# 612_jetracer.net
KiCad netlist of a schematic drawn in EAGLE
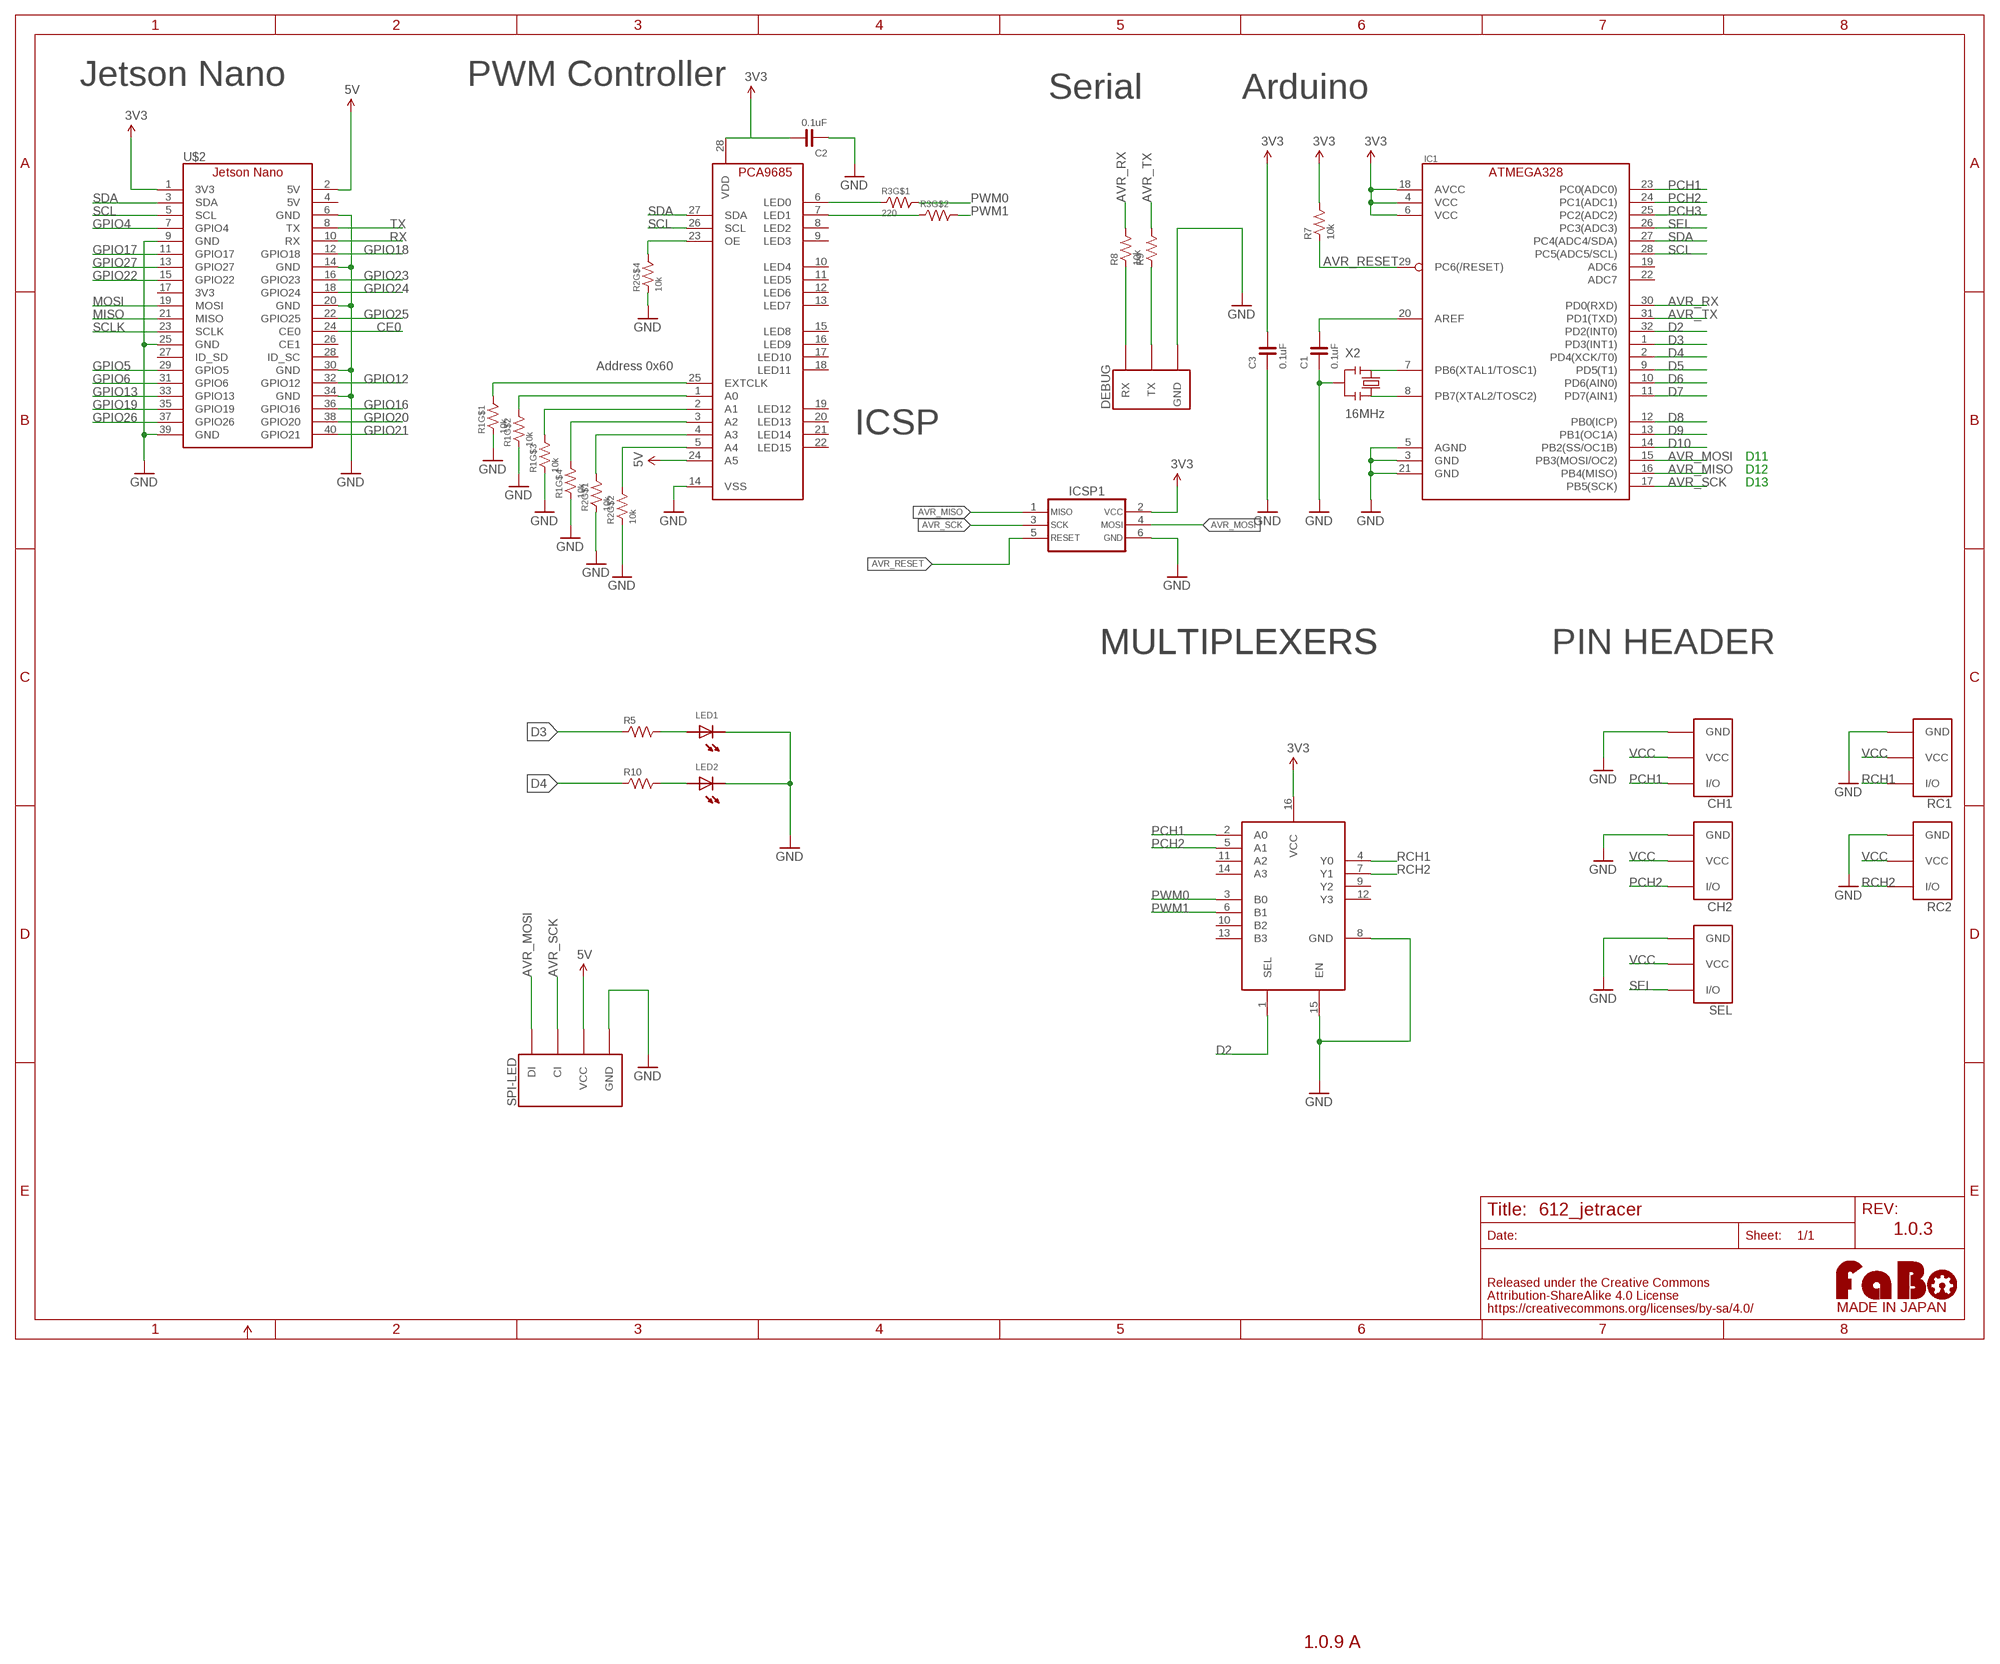
[diagram p0: schematic, sheet 1]

(export (version "E")
  (design (tool "Eeschema 10.0.6"))
  (components
    (comp (ref "C1")
      (value "0.1uF")
      (footprint "eagle-import:0603")
      (libsource (lib "eagle-import") (part "CAPACITOR-0603"))
    )
    (comp (ref "C2")
      (value "0.1uF")
      (footprint "eagle-import:0603")
      (libsource (lib "eagle-import") (part "CAPACITOR-0603"))
    )
    (comp (ref "C3")
      (value "0.1uF")
      (footprint "eagle-import:0603")
      (libsource (lib "eagle-import") (part "CAPACITOR-0603"))
    )
    (comp (ref "CH1")
      (value "FABO_BRICK_3PIN-HEADER")
      (footprint "eagle-import:FABO_BRICK_3PIN_HEADER")
      (libsource (lib "eagle-import") (part "FABO_BRICK_3PIN-HEADER"))
    )
    (comp (ref "CH2")
      (value "FABO_BRICK_3PIN-HEADER")
      (footprint "eagle-import:FABO_BRICK_3PIN_HEADER")
      (libsource (lib "eagle-import") (part "FABO_BRICK_3PIN-HEADER"))
    )
    (comp (ref "DEBUG")
      (value "FABO_BRICK_3PIN_DEBUG")
      (footprint "eagle-import:FABO_BRICK_3PIN_DEBUG")
      (libsource (lib "eagle-import") (part "FABO_BRICK_3PIN_DEBUG"))
    )
    (comp (ref "IC1")
      (value "ATMEGA328P-AU")
      (footprint "eagle-import:TQFP-32")
      (libsource (lib "eagle-import") (part "ATMEGA328P-AU"))
    )
    (comp (ref "IC3")
      (value "MULTIPLEXERSMC74HC157A")
      (footprint "eagle-import:TSSOP-16")
      (libsource (lib "eagle-import") (part "MULTIPLEXERSMC74HC157A"))
    )
    (comp (ref "ICSP1")
      (value "ICSP_AVR-TC_NOHOLE")
      (footprint "eagle-import:TC2030")
      (libsource (lib "eagle-import") (part "ICSP_AVR-TC_NOHOLE"))
    )
    (comp (ref "LED1")
      (value "LED-0603")
      (footprint "eagle-import:0603")
      (libsource (lib "eagle-import") (part "LED-0603"))
    )
    (comp (ref "LED2")
      (value "LED-0603")
      (footprint "eagle-import:0603")
      (libsource (lib "eagle-import") (part "LED-0603"))
    )
    (comp (ref "R1")
      (value "10k")
      (footprint "eagle-import:EXBV8V")
      (libsource (lib "eagle-import") (part "RESISTOR_ARRAY"))
    )
    (comp (ref "R2")
      (value "10k")
      (footprint "eagle-import:EXBV8V")
      (libsource (lib "eagle-import") (part "RESISTOR_ARRAY"))
    )
    (comp (ref "R3")
      (value "220")
      (footprint "eagle-import:EXBV8V")
      (libsource (lib "eagle-import") (part "RESISTOR_ARRAY"))
    )
    (comp (ref "R5")
      (value "10k")
      (footprint "eagle-import:0603")
      (libsource (lib "eagle-import") (part "RESISTOR-0603"))
    )
    (comp (ref "R7")
      (value "10k")
      (footprint "eagle-import:0603")
      (libsource (lib "eagle-import") (part "RESISTOR-0603"))
    )
    (comp (ref "R8")
      (value "10k")
      (footprint "eagle-import:0603")
      (libsource (lib "eagle-import") (part "RESISTOR-0603"))
    )
    (comp (ref "R9")
      (value "10k")
      (footprint "eagle-import:0603")
      (libsource (lib "eagle-import") (part "RESISTOR-0603"))
    )
    (comp (ref "R10")
      (value "10k")
      (footprint "eagle-import:0603")
      (libsource (lib "eagle-import") (part "RESISTOR-0603"))
    )
    (comp (ref "RC1")
      (value "FABO_BRICK_3PIN-HEADER")
      (footprint "eagle-import:FABO_BRICK_3PIN_HEADER")
      (libsource (lib "eagle-import") (part "FABO_BRICK_3PIN-HEADER"))
    )
    (comp (ref "RC2")
      (value "FABO_BRICK_3PIN-HEADER")
      (footprint "eagle-import:FABO_BRICK_3PIN_HEADER")
      (libsource (lib "eagle-import") (part "FABO_BRICK_3PIN-HEADER"))
    )
    (comp (ref "SEL")
      (value "FABO_BRICK_3PIN-HEADER")
      (footprint "eagle-import:FABO_BRICK_3PIN_HEADER")
      (libsource (lib "eagle-import") (part "FABO_BRICK_3PIN-HEADER"))
    )
    (comp (ref "SPI-LED")
      (value "FABO-SPI-LED-B04B")
      (footprint "eagle-import:SPI-B04B-PASK-1")
      (libsource (lib "eagle-import") (part "FABO-SPI-LED-B04B"))
    )
    (comp (ref "U$2")
      (value "JETSON_NANO_NOBORDER")
      (footprint "eagle-import:JETSON_NANO_NOBOARDER")
      (libsource (lib "eagle-import") (part "JETSON_NANO_NOBORDER"))
    )
    (comp (ref "U$9")
      (value "PCA9685")
      (footprint "eagle-import:PCA9685")
      (libsource (lib "eagle-import") (part "PCA9685"))
    )
    (comp (ref "U$14")
      (value "LOGO_FABO-M")
      (footprint "eagle-import:LOGO_FABO_MS")
      (libsource (lib "eagle-import") (part "LOGO_FABO-M"))
    )
    (comp (ref "X2")
      (value "16MHz")
      (footprint "eagle-import:CSTNE_V_C")
      (libsource (lib "eagle-import") (part "RESONATOR"))
    )
  )
  (nets
    (net (code "1") (name "/AVR_RX") (class "Default")
      (node (ref "IC1") (pin "30") (pinfunction "PD0(RXD)_30") (pintype "bidirectional"))
      (node (ref "R8") (pin "2") (pinfunction "2_2") (pintype "bidirectional"))
    )
    (net (code "2") (name "/AVR_TX") (class "Default")
      (node (ref "IC1") (pin "31") (pinfunction "PD1(TXD)_31") (pintype "bidirectional"))
      (node (ref "R9") (pin "2") (pinfunction "2_2") (pintype "bidirectional"))
    )
    (net (code "3") (name "/CE0") (class "Default")
      (node (ref "U$2") (pin "24") (pinfunction "CE0_24") (pintype "bidirectional"))
    )
    (net (code "4") (name "/D2") (class "Default")
      (node (ref "IC1") (pin "32") (pinfunction "PD2(INT0)_32") (pintype "bidirectional"))
      (node (ref "IC3") (pin "1") (pinfunction "SEL_1") (pintype "bidirectional"))
    )
    (net (code "5") (name "/D5") (class "Default")
      (node (ref "IC1") (pin "9") (pinfunction "PD5(T1)_9") (pintype "bidirectional"))
    )
    (net (code "6") (name "/D6") (class "Default")
      (node (ref "IC1") (pin "10") (pinfunction "PD6(AIN0)_10") (pintype "bidirectional"))
    )
    (net (code "7") (name "/D7") (class "Default")
      (node (ref "IC1") (pin "11") (pinfunction "PD7(AIN1)_11") (pintype "bidirectional"))
    )
    (net (code "8") (name "/D8") (class "Default")
      (node (ref "IC1") (pin "12") (pinfunction "PB0(ICP)_12") (pintype "bidirectional"))
    )
    (net (code "9") (name "/D9") (class "Default")
      (node (ref "IC1") (pin "13") (pinfunction "PB1(OC1A)_13") (pintype "bidirectional"))
    )
    (net (code "10") (name "/D10") (class "Default")
      (node (ref "IC1") (pin "14") (pinfunction "PB2(SS/OC1B)_14") (pintype "bidirectional"))
    )
    (net (code "11") (name "/GPIO4") (class "Default")
      (node (ref "U$2") (pin "7") (pinfunction "GPIO4_7") (pintype "bidirectional"))
    )
    (net (code "12") (name "/GPIO5") (class "Default")
      (node (ref "U$2") (pin "29") (pinfunction "GPIO5_29") (pintype "bidirectional"))
    )
    (net (code "13") (name "/GPIO6") (class "Default")
      (node (ref "U$2") (pin "31") (pinfunction "GPIO6_31") (pintype "bidirectional"))
    )
    (net (code "14") (name "/GPIO12") (class "Default")
      (node (ref "U$2") (pin "32") (pinfunction "GPIO12_32") (pintype "bidirectional"))
    )
    (net (code "15") (name "/GPIO13") (class "Default")
      (node (ref "U$2") (pin "33") (pinfunction "GPIO13_33") (pintype "bidirectional"))
    )
    (net (code "16") (name "/GPIO16") (class "Default")
      (node (ref "U$2") (pin "36") (pinfunction "GPIO16_36") (pintype "bidirectional"))
    )
    (net (code "17") (name "/GPIO17") (class "Default")
      (node (ref "U$2") (pin "11") (pinfunction "GPIO17_11") (pintype "bidirectional"))
    )
    (net (code "18") (name "/GPIO18") (class "Default")
      (node (ref "U$2") (pin "12") (pinfunction "GPIO18_12") (pintype "bidirectional"))
    )
    (net (code "19") (name "/GPIO19") (class "Default")
      (node (ref "U$2") (pin "35") (pinfunction "GPIO19_35") (pintype "bidirectional"))
    )
    (net (code "20") (name "/GPIO20") (class "Default")
      (node (ref "U$2") (pin "38") (pinfunction "GPIO20_38") (pintype "bidirectional"))
    )
    (net (code "21") (name "/GPIO21") (class "Default")
      (node (ref "U$2") (pin "40") (pinfunction "GPIO21_40") (pintype "bidirectional"))
    )
    (net (code "22") (name "/GPIO22") (class "Default")
      (node (ref "U$2") (pin "15") (pinfunction "GPIO22_15") (pintype "bidirectional"))
    )
    (net (code "23") (name "/GPIO23") (class "Default")
      (node (ref "U$2") (pin "16") (pinfunction "GPIO23_16") (pintype "bidirectional"))
    )
    (net (code "24") (name "/GPIO24") (class "Default")
      (node (ref "U$2") (pin "18") (pinfunction "GPIO24_18") (pintype "bidirectional"))
    )
    (net (code "25") (name "/GPIO25") (class "Default")
      (node (ref "U$2") (pin "22") (pinfunction "GPIO25_22") (pintype "bidirectional"))
    )
    (net (code "26") (name "/GPIO26") (class "Default")
      (node (ref "U$2") (pin "37") (pinfunction "GPIO26_37") (pintype "bidirectional"))
    )
    (net (code "27") (name "/GPIO27") (class "Default")
      (node (ref "U$2") (pin "13") (pinfunction "GPIO27_13") (pintype "bidirectional"))
    )
    (net (code "28") (name "/MISO") (class "Default")
      (node (ref "U$2") (pin "21") (pinfunction "MISO_21") (pintype "bidirectional"))
    )
    (net (code "29") (name "/MOSI") (class "Default")
      (node (ref "U$2") (pin "19") (pinfunction "MOSI_19") (pintype "bidirectional"))
    )
    (net (code "30") (name "/PCH1") (class "Default")
      (node (ref "CH1") (pin "I/O") (pinfunction "I/O_I/O") (pintype "bidirectional"))
      (node (ref "IC1") (pin "23") (pinfunction "PC0(ADC0)_23") (pintype "bidirectional"))
      (node (ref "IC3") (pin "2") (pinfunction "A0_2") (pintype "bidirectional"))
    )
    (net (code "31") (name "/PCH2") (class "Default")
      (node (ref "CH2") (pin "I/O") (pinfunction "I/O_I/O") (pintype "bidirectional"))
      (node (ref "IC1") (pin "24") (pinfunction "PC1(ADC1)_24") (pintype "bidirectional"))
      (node (ref "IC3") (pin "5") (pinfunction "A1_5") (pintype "bidirectional"))
    )
    (net (code "32") (name "/PCH3") (class "Default")
      (node (ref "IC1") (pin "25") (pinfunction "PC2(ADC2)_25") (pintype "bidirectional"))
    )
    (net (code "33") (name "/PWM0") (class "Default")
      (node (ref "IC3") (pin "3") (pinfunction "B0_3") (pintype "bidirectional"))
      (node (ref "R3") (pin "8") (pinfunction "2_8") (pintype "bidirectional"))
    )
    (net (code "34") (name "/PWM1") (class "Default")
      (node (ref "IC3") (pin "6") (pinfunction "B1_6") (pintype "bidirectional"))
      (node (ref "R3") (pin "7") (pinfunction "2_7") (pintype "bidirectional"))
    )
    (net (code "35") (name "/RCH1") (class "Default")
      (node (ref "IC3") (pin "4") (pinfunction "Y0_4") (pintype "bidirectional"))
      (node (ref "RC1") (pin "I/O") (pinfunction "I/O_I/O") (pintype "bidirectional"))
    )
    (net (code "36") (name "/RCH2") (class "Default")
      (node (ref "IC3") (pin "7") (pinfunction "Y1_7") (pintype "bidirectional"))
      (node (ref "RC2") (pin "I/O") (pinfunction "I/O_I/O") (pintype "bidirectional"))
    )
    (net (code "37") (name "/RX") (class "Default")
      (node (ref "U$2") (pin "10") (pinfunction "RX_10") (pintype "bidirectional"))
    )
    (net (code "38") (name "/SCL") (class "Default")
      (node (ref "IC1") (pin "28") (pinfunction "PC5(ADC5/SCL)_28") (pintype "bidirectional"))
      (node (ref "U$2") (pin "5") (pinfunction "SCL_5") (pintype "bidirectional"))
      (node (ref "U$9") (pin "26") (pinfunction "SCL_26") (pintype "bidirectional"))
    )
    (net (code "39") (name "/SCLK") (class "Default")
      (node (ref "U$2") (pin "23") (pinfunction "SCLK_23") (pintype "bidirectional"))
    )
    (net (code "40") (name "/SDA") (class "Default")
      (node (ref "IC1") (pin "27") (pinfunction "PC4(ADC4/SDA)_27") (pintype "bidirectional"))
      (node (ref "U$2") (pin "3") (pinfunction "SDA_3") (pintype "bidirectional"))
      (node (ref "U$9") (pin "27") (pinfunction "SDA_27") (pintype "bidirectional"))
    )
    (net (code "41") (name "/SEL") (class "Default")
      (node (ref "IC1") (pin "26") (pinfunction "PC3(ADC3)_26") (pintype "bidirectional"))
      (node (ref "SEL") (pin "I/O") (pinfunction "I/O_I/O") (pintype "bidirectional"))
    )
    (net (code "42") (name "/TX") (class "Default")
      (node (ref "U$2") (pin "8") (pinfunction "TX_8") (pintype "bidirectional"))
    )
    (net (code "43") (name "/VCC") (class "Default")
      (node (ref "CH1") (pin "VCC") (pinfunction "VCC_VCC") (pintype "bidirectional"))
      (node (ref "CH2") (pin "VCC") (pinfunction "VCC_VCC") (pintype "bidirectional"))
      (node (ref "RC1") (pin "VCC") (pinfunction "VCC_VCC") (pintype "bidirectional"))
      (node (ref "RC2") (pin "VCC") (pinfunction "VCC_VCC") (pintype "bidirectional"))
      (node (ref "SEL") (pin "VCC") (pinfunction "VCC_VCC") (pintype "bidirectional"))
    )
    (net (code "44") (name "3V3") (class "Default")
      (node (ref "C2") (pin "2") (pinfunction "2_2") (pintype "passive"))
      (node (ref "C3") (pin "2") (pinfunction "2_2") (pintype "passive"))
      (node (ref "IC1") (pin "18") (pinfunction "AVCC_18") (pintype "bidirectional"))
      (node (ref "IC1") (pin "4") (pinfunction "VCC_4") (pintype "bidirectional"))
      (node (ref "IC1") (pin "6") (pinfunction "VCC_6") (pintype "bidirectional"))
      (node (ref "IC3") (pin "16") (pinfunction "VCC_16") (pintype "bidirectional"))
      (node (ref "ICSP1") (pin "2") (pinfunction "2_2") (pintype "passive"))
      (node (ref "R7") (pin "2") (pinfunction "2_2") (pintype "bidirectional"))
      (node (ref "U$2") (pin "1") (pinfunction "3V3_1") (pintype "bidirectional"))
      (node (ref "U$9") (pin "28") (pinfunction "VDD_28") (pintype "bidirectional"))
    )
    (net (code "45") (name "5V") (class "Default")
      (node (ref "SPI-LED") (pin "VCC") (pinfunction "VCC_VCC") (pintype "bidirectional"))
      (node (ref "U$2") (pin "2") (pinfunction "5V_2") (pintype "bidirectional"))
      (node (ref "U$9") (pin "24") (pinfunction "A5_24") (pintype "bidirectional"))
    )
    (net (code "46") (name "AVR_MISO") (class "Default")
      (node (ref "IC1") (pin "16") (pinfunction "PB4(MISO)_16") (pintype "bidirectional"))
      (node (ref "ICSP1") (pin "1") (pinfunction "1_1") (pintype "passive"))
    )
    (net (code "47") (name "AVR_MOSI") (class "Default")
      (node (ref "IC1") (pin "15") (pinfunction "PB3(MOSI/OC2)_15") (pintype "bidirectional"))
      (node (ref "ICSP1") (pin "4") (pinfunction "4_4") (pintype "passive"))
      (node (ref "SPI-LED") (pin "DI") (pinfunction "DI_DI") (pintype "bidirectional"))
    )
    (net (code "48") (name "AVR_RESET") (class "Default")
      (node (ref "IC1") (pin "29") (pinfunction "PC6(/RESET)_29") (pintype "bidirectional"))
      (node (ref "ICSP1") (pin "5") (pinfunction "5_5") (pintype "passive"))
      (node (ref "R7") (pin "1") (pinfunction "1_1") (pintype "bidirectional"))
    )
    (net (code "49") (name "AVR_SCK") (class "Default")
      (node (ref "IC1") (pin "17") (pinfunction "PB5(SCK)_17") (pintype "bidirectional"))
      (node (ref "ICSP1") (pin "3") (pinfunction "3_3") (pintype "passive"))
      (node (ref "SPI-LED") (pin "CI") (pinfunction "CI_CI") (pintype "bidirectional"))
    )
    (net (code "50") (name "D3") (class "Default")
      (node (ref "IC1") (pin "1") (pinfunction "PD3(INT1)_1") (pintype "bidirectional"))
      (node (ref "R5") (pin "1") (pinfunction "1_1") (pintype "bidirectional"))
    )
    (net (code "51") (name "D4") (class "Default")
      (node (ref "IC1") (pin "2") (pinfunction "PD4(XCK/T0)_2") (pintype "bidirectional"))
      (node (ref "R10") (pin "1") (pinfunction "1_1") (pintype "bidirectional"))
    )
    (net (code "52") (name "GND") (class "Default")
      (node (ref "C1") (pin "1") (pinfunction "1_1") (pintype "passive"))
      (node (ref "C2") (pin "1") (pinfunction "1_1") (pintype "passive"))
      (node (ref "C3") (pin "1") (pinfunction "1_1") (pintype "passive"))
      (node (ref "CH1") (pin "GND") (pinfunction "GND_GND") (pintype "bidirectional"))
      (node (ref "CH2") (pin "GND") (pinfunction "GND_GND") (pintype "bidirectional"))
      (node (ref "DEBUG") (pin "GND") (pinfunction "GND_GND") (pintype "bidirectional"))
      (node (ref "IC1") (pin "21") (pinfunction "GND_21") (pintype "bidirectional"))
      (node (ref "IC1") (pin "3") (pinfunction "GND_3") (pintype "bidirectional"))
      (node (ref "IC1") (pin "5") (pinfunction "AGND_5") (pintype "bidirectional"))
      (node (ref "IC3") (pin "15") (pinfunction "EN_15") (pintype "bidirectional"))
      (node (ref "IC3") (pin "8") (pinfunction "GND_8") (pintype "bidirectional"))
      (node (ref "ICSP1") (pin "6") (pinfunction "6_6") (pintype "passive"))
      (node (ref "LED1") (pin "CATHODE") (pinfunction "CATHODE_CATHODE") (pintype "passive"))
      (node (ref "LED2") (pin "CATHODE") (pinfunction "CATHODE_CATHODE") (pintype "passive"))
      (node (ref "R1") (pin "1") (pinfunction "1_1") (pintype "bidirectional"))
      (node (ref "R1") (pin "2") (pinfunction "1_2") (pintype "bidirectional"))
      (node (ref "R1") (pin "3") (pinfunction "1_3") (pintype "bidirectional"))
      (node (ref "R1") (pin "4") (pinfunction "1_4") (pintype "bidirectional"))
      (node (ref "R2") (pin "1") (pinfunction "1_1") (pintype "bidirectional"))
      (node (ref "R2") (pin "2") (pinfunction "1_2") (pintype "bidirectional"))
      (node (ref "R2") (pin "4") (pinfunction "1_4") (pintype "bidirectional"))
      (node (ref "RC1") (pin "GND") (pinfunction "GND_GND") (pintype "bidirectional"))
      (node (ref "RC2") (pin "GND") (pinfunction "GND_GND") (pintype "bidirectional"))
      (node (ref "SEL") (pin "GND") (pinfunction "GND_GND") (pintype "bidirectional"))
      (node (ref "SPI-LED") (pin "GND") (pinfunction "GND_GND") (pintype "bidirectional"))
      (node (ref "U$2") (pin "14") (pinfunction "GND_14") (pintype "bidirectional"))
      (node (ref "U$2") (pin "20") (pinfunction "GND_20") (pintype "bidirectional"))
      (node (ref "U$2") (pin "25") (pinfunction "GND_25") (pintype "bidirectional"))
      (node (ref "U$2") (pin "30") (pinfunction "GND_30") (pintype "bidirectional"))
      (node (ref "U$2") (pin "34") (pinfunction "GND_34") (pintype "bidirectional"))
      (node (ref "U$2") (pin "39") (pinfunction "GND_39") (pintype "bidirectional"))
      (node (ref "U$2") (pin "6") (pinfunction "GND_6") (pintype "bidirectional"))
      (node (ref "U$2") (pin "9") (pinfunction "GND_9") (pintype "bidirectional"))
      (node (ref "U$9") (pin "14") (pinfunction "VSS_14") (pintype "bidirectional"))
      (node (ref "X2") (pin "2") (pinfunction "2_2") (pintype "passive"))
    )
    (net (code "53") (name "Net-(DEBUG-PadRX)") (class "Default")
      (node (ref "DEBUG") (pin "RX") (pinfunction "RX_RX") (pintype "bidirectional"))
      (node (ref "R8") (pin "1") (pinfunction "1_1") (pintype "bidirectional"))
    )
    (net (code "54") (name "Net-(DEBUG-PadTX)") (class "Default")
      (node (ref "DEBUG") (pin "TX") (pinfunction "TX_TX") (pintype "bidirectional"))
      (node (ref "R9") (pin "1") (pinfunction "1_1") (pintype "bidirectional"))
    )
    (net (code "55") (name "Net-(IC1-AREF)") (class "Default")
      (node (ref "C1") (pin "2") (pinfunction "2_2") (pintype "passive"))
      (node (ref "IC1") (pin "20") (pinfunction "AREF_20") (pintype "bidirectional"))
    )
    (net (code "56") (name "Net-(IC1-PB6(XTAL1{slash}TOSC1))") (class "Default")
      (node (ref "IC1") (pin "7") (pinfunction "PB6(XTAL1/TOSC1)_7") (pintype "bidirectional"))
      (node (ref "X2") (pin "1") (pinfunction "1_1") (pintype "passive"))
    )
    (net (code "57") (name "Net-(IC1-PB7(XTAL2{slash}TOSC2))") (class "Default")
      (node (ref "IC1") (pin "8") (pinfunction "PB7(XTAL2/TOSC2)_8") (pintype "bidirectional"))
      (node (ref "X2") (pin "3") (pinfunction "3_3") (pintype "passive"))
    )
    (net (code "58") (name "Net-(LED1-PadANODE)") (class "Default")
      (node (ref "LED1") (pin "ANODE") (pinfunction "ANODE_ANODE") (pintype "passive"))
      (node (ref "R5") (pin "2") (pinfunction "2_2") (pintype "bidirectional"))
    )
    (net (code "59") (name "Net-(LED2-PadANODE)") (class "Default")
      (node (ref "LED2") (pin "ANODE") (pinfunction "ANODE_ANODE") (pintype "passive"))
      (node (ref "R10") (pin "2") (pinfunction "2_2") (pintype "bidirectional"))
    )
    (net (code "60") (name "Net-(R1A-2)") (class "Default")
      (node (ref "R1") (pin "8") (pinfunction "2_8") (pintype "bidirectional"))
      (node (ref "U$9") (pin "25") (pinfunction "EXTCLK_25") (pintype "bidirectional"))
    )
    (net (code "61") (name "Net-(R1B-2)") (class "Default")
      (node (ref "R1") (pin "7") (pinfunction "2_7") (pintype "bidirectional"))
      (node (ref "U$9") (pin "1") (pinfunction "A0_1") (pintype "bidirectional"))
    )
    (net (code "62") (name "Net-(R1C-2)") (class "Default")
      (node (ref "R1") (pin "6") (pinfunction "2_6") (pintype "bidirectional"))
      (node (ref "U$9") (pin "2") (pinfunction "A1_2") (pintype "bidirectional"))
    )
    (net (code "63") (name "Net-(R1D-2)") (class "Default")
      (node (ref "R1") (pin "5") (pinfunction "2_5") (pintype "bidirectional"))
      (node (ref "U$9") (pin "3") (pinfunction "A2_3") (pintype "bidirectional"))
    )
    (net (code "64") (name "Net-(R2A-2)") (class "Default")
      (node (ref "R2") (pin "8") (pinfunction "2_8") (pintype "bidirectional"))
      (node (ref "U$9") (pin "4") (pinfunction "A3_4") (pintype "bidirectional"))
    )
    (net (code "65") (name "Net-(R2B-2)") (class "Default")
      (node (ref "R2") (pin "7") (pinfunction "2_7") (pintype "bidirectional"))
      (node (ref "U$9") (pin "5") (pinfunction "A4_5") (pintype "bidirectional"))
    )
    (net (code "66") (name "Net-(R2D-2)") (class "Default")
      (node (ref "R2") (pin "5") (pinfunction "2_5") (pintype "bidirectional"))
      (node (ref "U$9") (pin "23") (pinfunction "OE_23") (pintype "bidirectional"))
    )
    (net (code "67") (name "Net-(R3B-1)") (class "Default")
      (node (ref "R3") (pin "2") (pinfunction "1_2") (pintype "bidirectional"))
      (node (ref "U$9") (pin "7") (pinfunction "LED1_7") (pintype "bidirectional"))
    )
    (net (code "68") (name "Net-(U$9-LED0)") (class "Default")
      (node (ref "R3") (pin "1") (pinfunction "1_1") (pintype "bidirectional"))
      (node (ref "U$9") (pin "6") (pinfunction "LED0_6") (pintype "bidirectional"))
    )
    (net (code "69") (name "unconnected-(IC1-ADC6-Pad19)") (class "Default")
      (node (ref "IC1") (pin "19") (pinfunction "ADC6_19") (pintype "bidirectional"))
    )
    (net (code "70") (name "unconnected-(IC1-ADC7-Pad22)") (class "Default")
      (node (ref "IC1") (pin "22") (pinfunction "ADC7_22") (pintype "bidirectional"))
    )
    (net (code "71") (name "unconnected-(IC3-A2-Pad11)") (class "Default")
      (node (ref "IC3") (pin "11") (pinfunction "A2_11") (pintype "bidirectional"))
    )
    (net (code "72") (name "unconnected-(IC3-A3-Pad14)") (class "Default")
      (node (ref "IC3") (pin "14") (pinfunction "A3_14") (pintype "bidirectional"))
    )
    (net (code "73") (name "unconnected-(IC3-B2-Pad10)") (class "Default")
      (node (ref "IC3") (pin "10") (pinfunction "B2_10") (pintype "bidirectional"))
    )
    (net (code "74") (name "unconnected-(IC3-B3-Pad13)") (class "Default")
      (node (ref "IC3") (pin "13") (pinfunction "B3_13") (pintype "bidirectional"))
    )
    (net (code "75") (name "unconnected-(IC3-Y2-Pad9)") (class "Default")
      (node (ref "IC3") (pin "9") (pinfunction "Y2_9") (pintype "bidirectional"))
    )
    (net (code "76") (name "unconnected-(IC3-Y3-Pad12)") (class "Default")
      (node (ref "IC3") (pin "12") (pinfunction "Y3_12") (pintype "bidirectional"))
    )
    (net (code "77") (name "unconnected-(U$2-3V3-Pad17)") (class "Default")
      (node (ref "U$2") (pin "17") (pinfunction "3V3_17") (pintype "bidirectional"))
    )
    (net (code "78") (name "unconnected-(U$2-5V-Pad4)") (class "Default")
      (node (ref "U$2") (pin "4") (pinfunction "5V_4") (pintype "bidirectional"))
    )
    (net (code "79") (name "unconnected-(U$2-CE1-Pad26)") (class "Default")
      (node (ref "U$2") (pin "26") (pinfunction "CE1_26") (pintype "bidirectional"))
    )
    (net (code "80") (name "unconnected-(U$2-ID_SC-Pad28)") (class "Default")
      (node (ref "U$2") (pin "28") (pinfunction "ID_SC_28") (pintype "bidirectional"))
    )
    (net (code "81") (name "unconnected-(U$2-ID_SD-Pad27)") (class "Default")
      (node (ref "U$2") (pin "27") (pinfunction "ID_SD_27") (pintype "bidirectional"))
    )
    (net (code "82") (name "unconnected-(U$9-LED2-Pad8)") (class "Default")
      (node (ref "U$9") (pin "8") (pinfunction "LED2_8") (pintype "bidirectional"))
    )
    (net (code "83") (name "unconnected-(U$9-LED3-Pad9)") (class "Default")
      (node (ref "U$9") (pin "9") (pinfunction "LED3_9") (pintype "bidirectional"))
    )
    (net (code "84") (name "unconnected-(U$9-LED4-Pad10)") (class "Default")
      (node (ref "U$9") (pin "10") (pinfunction "LED4_10") (pintype "bidirectional"))
    )
    (net (code "85") (name "unconnected-(U$9-LED5-Pad11)") (class "Default")
      (node (ref "U$9") (pin "11") (pinfunction "LED5_11") (pintype "bidirectional"))
    )
    (net (code "86") (name "unconnected-(U$9-LED6-Pad12)") (class "Default")
      (node (ref "U$9") (pin "12") (pinfunction "LED6_12") (pintype "bidirectional"))
    )
    (net (code "87") (name "unconnected-(U$9-LED7-Pad13)") (class "Default")
      (node (ref "U$9") (pin "13") (pinfunction "LED7_13") (pintype "bidirectional"))
    )
    (net (code "88") (name "unconnected-(U$9-LED8-Pad15)") (class "Default")
      (node (ref "U$9") (pin "15") (pinfunction "LED8_15") (pintype "bidirectional"))
    )
    (net (code "89") (name "unconnected-(U$9-LED9-Pad16)") (class "Default")
      (node (ref "U$9") (pin "16") (pinfunction "LED9_16") (pintype "bidirectional"))
    )
    (net (code "90") (name "unconnected-(U$9-LED10-Pad17)") (class "Default")
      (node (ref "U$9") (pin "17") (pinfunction "LED10_17") (pintype "bidirectional"))
    )
    (net (code "91") (name "unconnected-(U$9-LED11-Pad18)") (class "Default")
      (node (ref "U$9") (pin "18") (pinfunction "LED11_18") (pintype "bidirectional"))
    )
    (net (code "92") (name "unconnected-(U$9-LED12-Pad19)") (class "Default")
      (node (ref "U$9") (pin "19") (pinfunction "LED12_19") (pintype "bidirectional"))
    )
    (net (code "93") (name "unconnected-(U$9-LED13-Pad20)") (class "Default")
      (node (ref "U$9") (pin "20") (pinfunction "LED13_20") (pintype "bidirectional"))
    )
    (net (code "94") (name "unconnected-(U$9-LED14-Pad21)") (class "Default")
      (node (ref "U$9") (pin "21") (pinfunction "LED14_21") (pintype "bidirectional"))
    )
    (net (code "95") (name "unconnected-(U$9-LED15-Pad22)") (class "Default")
      (node (ref "U$9") (pin "22") (pinfunction "LED15_22") (pintype "bidirectional"))
    )
  )
)
